# MCU_STM32H723ZGT6.net
KiCad netlist of a schematic drawn in Altium Designer
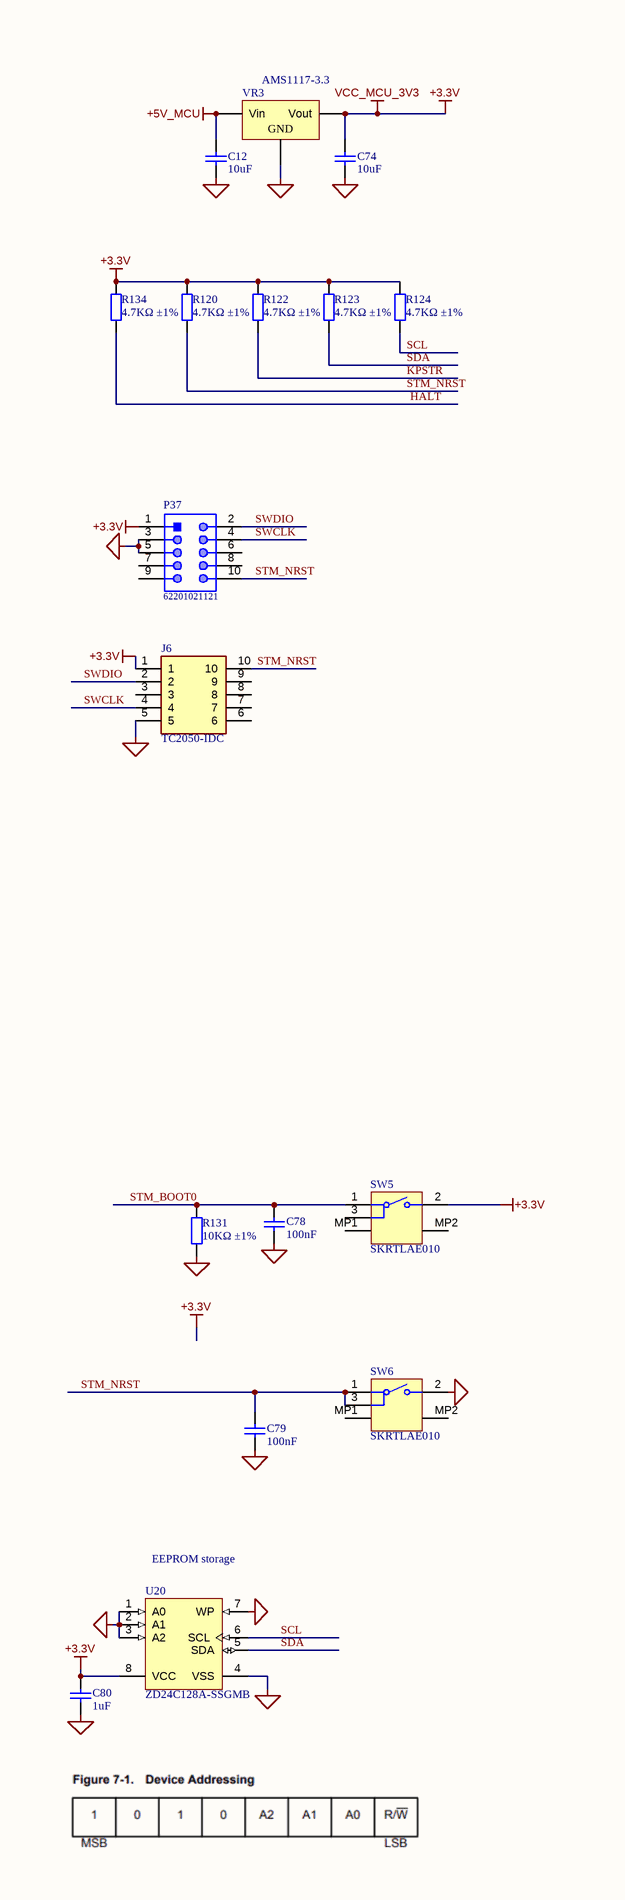
[diagram p0: MCU_STM32H723ZGT6.SchDoc, left]
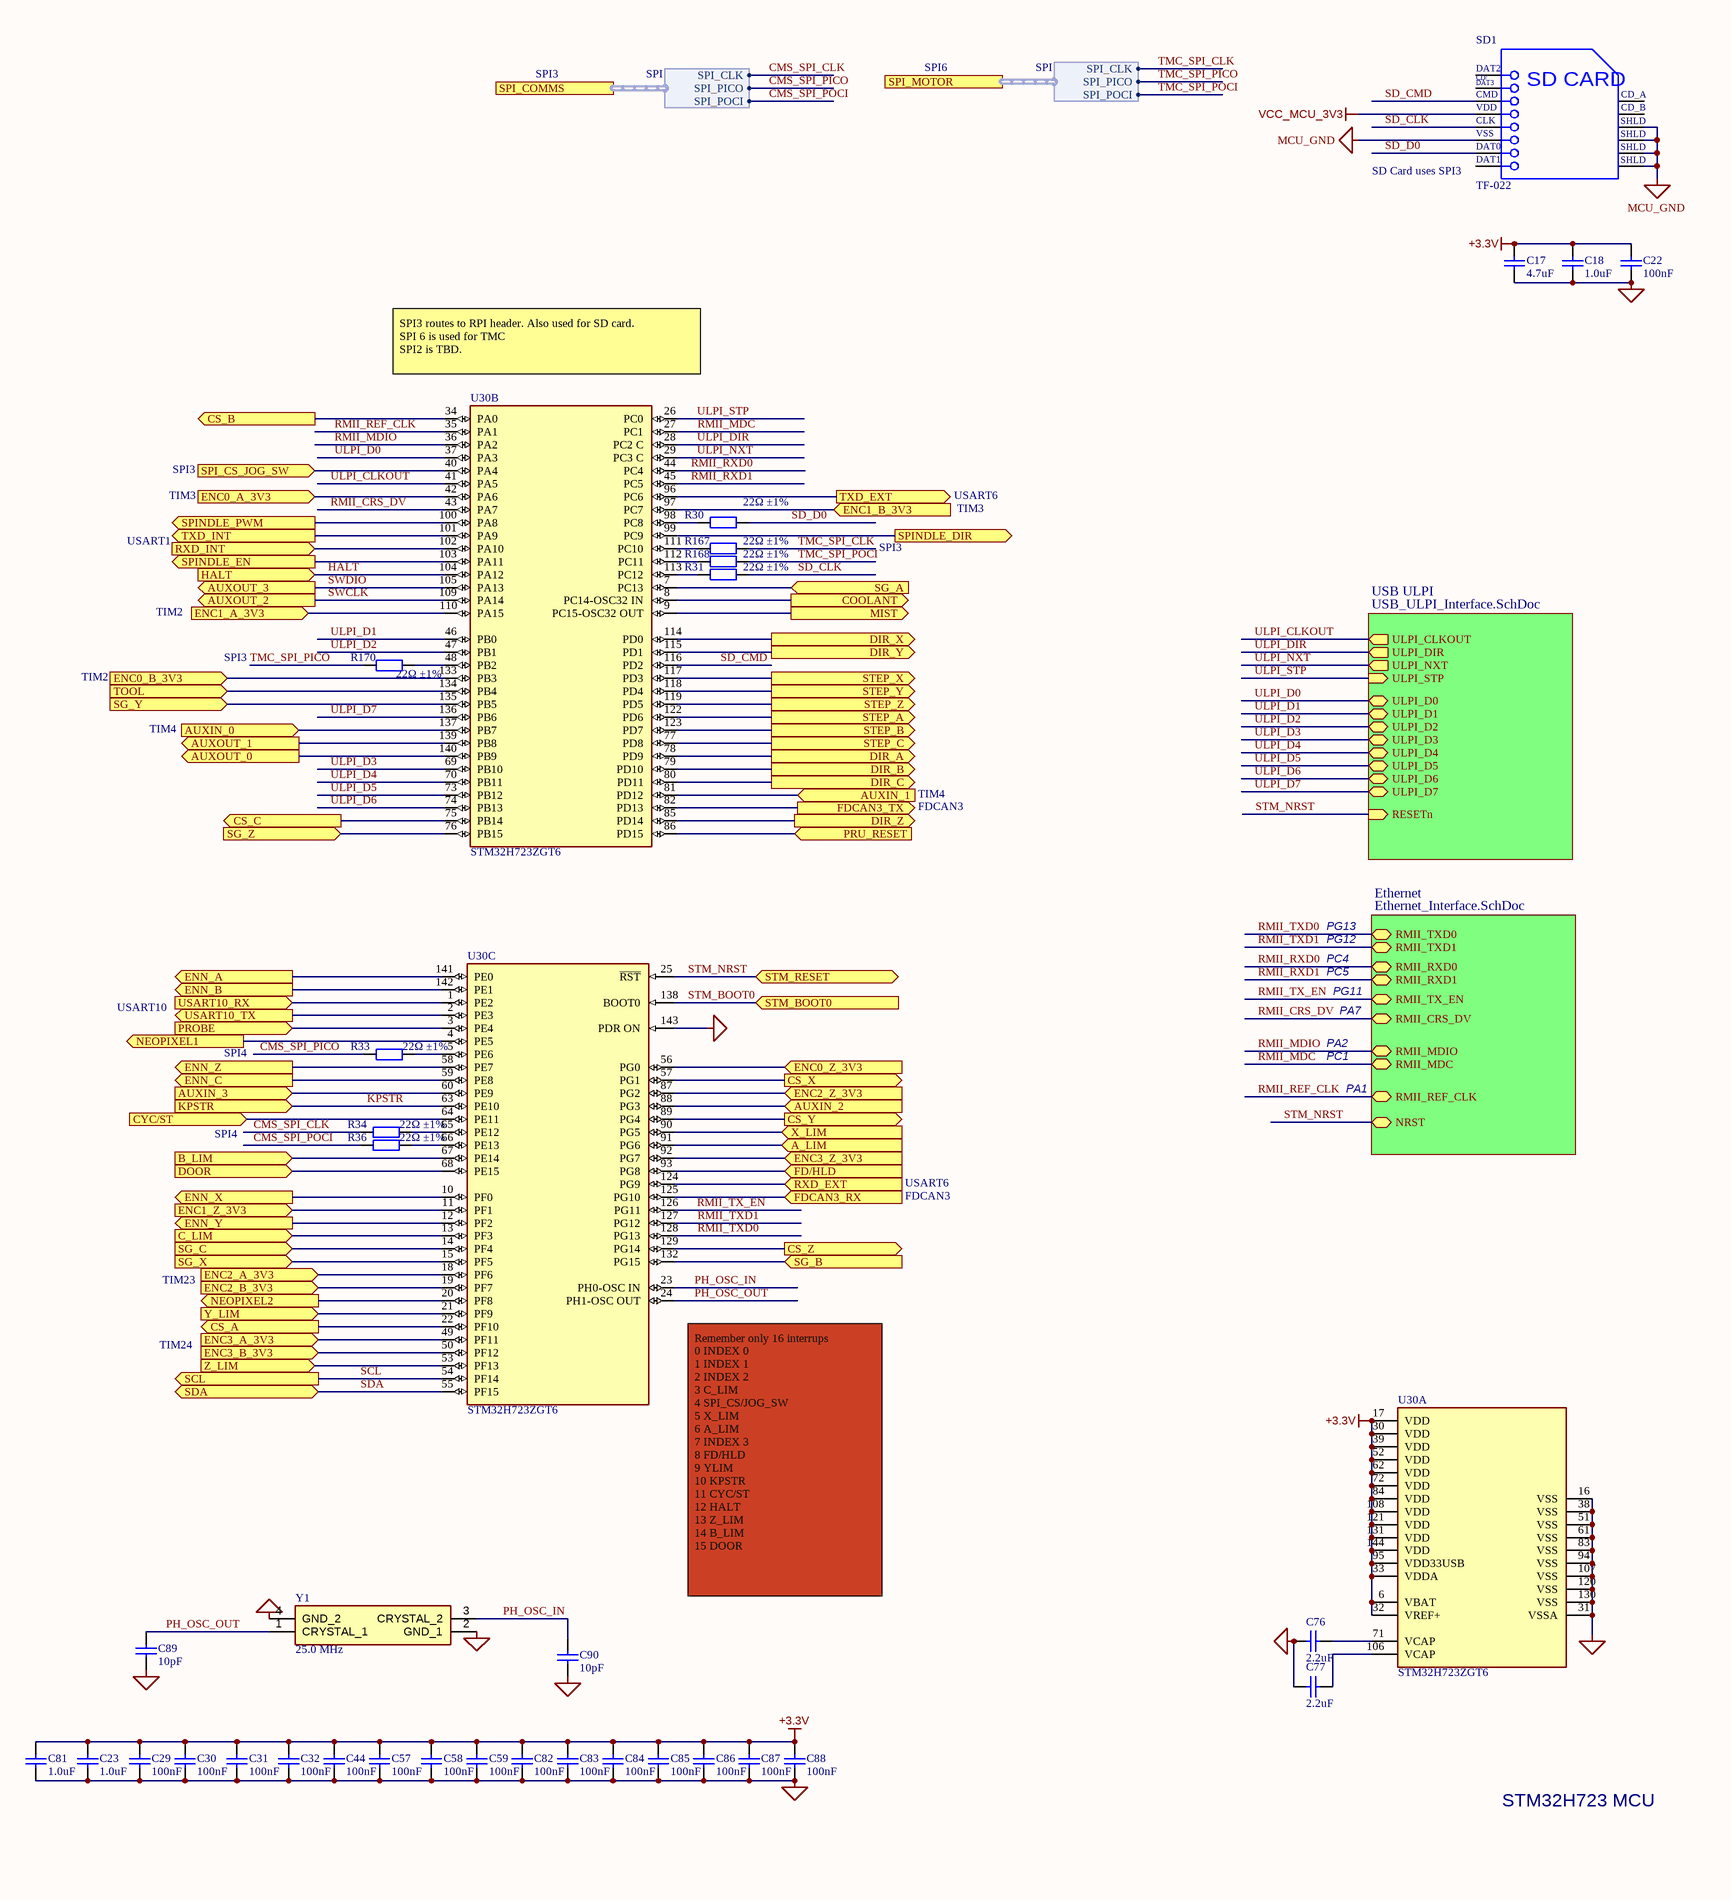
[diagram p1: MCU_STM32H723ZGT6.SchDoc, right]

(export (version "E")
  (design (tool "Eeschema 10.0.6"))
  (components
    (comp (ref "C12")
      (value "10uF")
      (footprint "1206_C")
      (description "Chip capacitors")
      (fields
        (field (name "MANUFACTURER") "Samsung Electro-Mechanics")
        (field (name "PARTNUMBER") "CL31A106KBHNNNE")
      )
      (libsource (lib "Cap") (part "1206 10uF (106) 10% 50V"))
    )
    (comp (ref "C17")
      (value "4.7uF")
      (footprint "0603_C")
      (description "16V 4.7uF X5R ±10% 0603 Multilayer Ceramic Capacitors MLCC - SMD/SMT ROHS")
      (fields (field (name "MANUFACTURER") "Samsung Electro-Mechanics") (field (name "TOLERANCE") "10%"))
      (libsource (lib "Sienci_Labs") (part "0603 4.7uF (475) 10% 16V"))
    )
    (comp (ref "C18")
      (value "1.0uF")
      (footprint "0402_C")
      (description "Chip capacitor")
      (fields (field (name "MANUFACTURER") "Samsung Electro-Mechanics") (field (name "TOLERANCE") "10%"))
      (libsource (lib "Cap") (part "0402 1.0uF (105) 10% 25V"))
    )
    (comp (ref "C22")
      (value "100nF")
      (footprint "0402_C")
      (description "16V 100nF X7R ±10% 0402 Multilayer Ceramic Capacitors MLCC - SMD/SMT ROHS")
      (fields (field (name "MANUFACTURER") "Samsung Electro-Mechanics") (field (name "TOLERANCE") "10%"))
      (libsource (lib "Sienci_Labs") (part "0402 100nF (104) 10% 16V"))
    )
    (comp (ref "C23")
      (value "1.0uF")
      (footprint "0402_C")
      (description "Chip capacitor")
      (fields
        (field (name "MANUFACTURER") "Samsung Electro-Mechanics")
        (field (name "PARTNUMBER") "CL05A105KA5NQNC")
      )
      (libsource (lib "Cap") (part "0402 1.0uF (105) 10% 25V"))
    )
    (comp (ref "C29")
      (value "100nF")
      (footprint "0402_C")
      (description "Chip capacitors")
      (fields
        (field (name "MANUFACTURER") "Samsung Electro-Mechanics")
        (field (name "PARTNUMBER") "CL05B104KO5NNNC")
      )
      (libsource (lib "Cap") (part "0402 100nF (104) 10% 16V"))
    )
    (comp (ref "C30")
      (value "100nF")
      (footprint "0402_C")
      (description "Chip capacitors")
      (fields
        (field (name "MANUFACTURER") "Samsung Electro-Mechanics")
        (field (name "PARTNUMBER") "CL05B104KO5NNNC")
      )
      (libsource (lib "Cap") (part "0402 100nF (104) 10% 16V"))
    )
    (comp (ref "C31")
      (value "100nF")
      (footprint "0402_C")
      (description "Chip capacitors")
      (fields
        (field (name "MANUFACTURER") "Samsung Electro-Mechanics")
        (field (name "PARTNUMBER") "CL05B104KO5NNNC")
      )
      (libsource (lib "Cap") (part "0402 100nF (104) 10% 16V"))
    )
    (comp (ref "C32")
      (value "100nF")
      (footprint "0402_C")
      (description "Chip capacitors")
      (fields
        (field (name "MANUFACTURER") "Samsung Electro-Mechanics")
        (field (name "PARTNUMBER") "CL05B104KO5NNNC")
      )
      (libsource (lib "Cap") (part "0402 100nF (104) 10% 16V"))
    )
    (comp (ref "C44")
      (value "100nF")
      (footprint "0402_C")
      (description "Chip capacitors")
      (fields
        (field (name "MANUFACTURER") "Samsung Electro-Mechanics")
        (field (name "PARTNUMBER") "CL05B104KO5NNNC")
      )
      (libsource (lib "Cap") (part "0402 100nF (104) 10% 16V"))
    )
    (comp (ref "C57")
      (value "100nF")
      (footprint "0402_C")
      (description "Chip capacitors")
      (fields
        (field (name "MANUFACTURER") "Samsung Electro-Mechanics")
        (field (name "PARTNUMBER") "CL05B104KO5NNNC")
      )
      (libsource (lib "Cap") (part "0402 100nF (104) 10% 16V"))
    )
    (comp (ref "C58")
      (value "100nF")
      (footprint "0402_C")
      (description "Chip capacitors")
      (fields
        (field (name "MANUFACTURER") "Samsung Electro-Mechanics")
        (field (name "PARTNUMBER") "CL05B104KO5NNNC")
      )
      (libsource (lib "Cap") (part "0402 100nF (104) 10% 16V"))
    )
    (comp (ref "C59")
      (value "100nF")
      (footprint "0402_C")
      (description "Chip capacitors")
      (fields
        (field (name "MANUFACTURER") "Samsung Electro-Mechanics")
        (field (name "PARTNUMBER") "CL05B104KO5NNNC")
      )
      (libsource (lib "Cap") (part "0402 100nF (104) 10% 16V"))
    )
    (comp (ref "C74")
      (value "10uF")
      (footprint "1206_C")
      (description "Chip capacitors")
      (fields
        (field (name "MANUFACTURER") "Samsung Electro-Mechanics")
        (field (name "PARTNUMBER") "CL31A106KBHNNNE")
      )
      (libsource (lib "Cap") (part "1206 10uF (106) 10% 50V"))
    )
    (comp (ref "C76")
      (value "2.2uF")
      (footprint "0603_C")
      (description "Chip capacitors")
      (fields
        (field (name "MANUFACTURER") "Samsung Electro-Mechanics")
        (field (name "PARTNUMBER") "CL10A225KO8NNNC")
      )
      (libsource (lib "Cap") (part "0603 2.2uF (225) 10% 16V"))
    )
    (comp (ref "C77")
      (value "2.2uF")
      (footprint "0603_C")
      (description "Chip capacitors")
      (fields
        (field (name "MANUFACTURER") "Samsung Electro-Mechanics")
        (field (name "PARTNUMBER") "CL10A225KO8NNNC")
      )
      (libsource (lib "Cap") (part "0603 2.2uF (225) 10% 16V"))
    )
    (comp (ref "C78")
      (value "100nF")
      (footprint "0603_C")
      (description "Chip capacitors")
      (fields (field (name "MANUFACTURER") "YAGEO") (field (name "PARTNUMBER") "CC0603KRX7R9BB104"))
      (libsource (lib "Cap") (part "0603 100nF (104) 10% 50V"))
    )
    (comp (ref "C79")
      (value "100nF")
      (footprint "0603_C")
      (description "Chip capacitors")
      (fields (field (name "MANUFACTURER") "YAGEO") (field (name "PARTNUMBER") "CC0603KRX7R9BB104"))
      (libsource (lib "Cap") (part "0603 100nF (104) 10% 50V"))
    )
    (comp (ref "C80")
      (value "1uF")
      (footprint "0603_C")
      (description "Chip capacitors")
      (fields
        (field (name "MANUFACTURER") "Samsung Electro-Mechanics")
        (field (name "PARTNUMBER") "CL10A105KB8NNNC")
      )
      (libsource (lib "Cap") (part "0603 1uF (105) 10% 50V"))
    )
    (comp (ref "C81")
      (value "1.0uF")
      (footprint "0402_C")
      (description "Chip capacitor")
      (fields
        (field (name "MANUFACTURER") "Samsung Electro-Mechanics")
        (field (name "PARTNUMBER") "CL05A105KA5NQNC")
      )
      (libsource (lib "Cap") (part "0402 1.0uF (105) 10% 25V"))
    )
    (comp (ref "C82")
      (value "100nF")
      (footprint "0402_C")
      (description "Chip capacitors")
      (fields
        (field (name "MANUFACTURER") "Samsung Electro-Mechanics")
        (field (name "PARTNUMBER") "CL05B104KO5NNNC")
      )
      (libsource (lib "Cap") (part "0402 100nF (104) 10% 16V"))
    )
    (comp (ref "C83")
      (value "100nF")
      (footprint "0402_C")
      (description "Chip capacitors")
      (fields
        (field (name "MANUFACTURER") "Samsung Electro-Mechanics")
        (field (name "PARTNUMBER") "CL05B104KO5NNNC")
      )
      (libsource (lib "Cap") (part "0402 100nF (104) 10% 16V"))
    )
    (comp (ref "C84")
      (value "100nF")
      (footprint "0402_C")
      (description "Chip capacitors")
      (fields
        (field (name "MANUFACTURER") "Samsung Electro-Mechanics")
        (field (name "PARTNUMBER") "CL05B104KO5NNNC")
      )
      (libsource (lib "Cap") (part "0402 100nF (104) 10% 16V"))
    )
    (comp (ref "C85")
      (value "100nF")
      (footprint "0402_C")
      (description "Chip capacitors")
      (fields
        (field (name "MANUFACTURER") "Samsung Electro-Mechanics")
        (field (name "PARTNUMBER") "CL05B104KO5NNNC")
      )
      (libsource (lib "Cap") (part "0402 100nF (104) 10% 16V"))
    )
    (comp (ref "C86")
      (value "100nF")
      (footprint "0402_C")
      (description "Chip capacitors")
      (fields
        (field (name "MANUFACTURER") "Samsung Electro-Mechanics")
        (field (name "PARTNUMBER") "CL05B104KO5NNNC")
      )
      (libsource (lib "Cap") (part "0402 100nF (104) 10% 16V"))
    )
    (comp (ref "C87")
      (value "100nF")
      (footprint "0402_C")
      (description "Chip capacitors")
      (fields
        (field (name "MANUFACTURER") "Samsung Electro-Mechanics")
        (field (name "PARTNUMBER") "CL05B104KO5NNNC")
      )
      (libsource (lib "Cap") (part "0402 100nF (104) 10% 16V"))
    )
    (comp (ref "C88")
      (value "100nF")
      (footprint "0402_C")
      (description "Chip capacitors")
      (fields
        (field (name "MANUFACTURER") "Samsung Electro-Mechanics")
        (field (name "PARTNUMBER") "CL05B104KO5NNNC")
      )
      (libsource (lib "Cap") (part "0402 100nF (104) 10% 16V"))
    )
    (comp (ref "C89")
      (value "10pF")
      (footprint "0402_C")
      (description "Chip capacitors")
      (fields
        (field (name "MANUFACTURER") "Samsung Electro-Mechanics")
        (field (name "PARTNUMBER") "CL05C100JB5NNNC")
      )
      (libsource (lib "Cap") (part "0402 10pF (100) 5% 50V"))
    )
    (comp (ref "C90")
      (value "10pF")
      (footprint "0402_C")
      (description "Chip capacitors")
      (fields
        (field (name "MANUFACTURER") "Samsung Electro-Mechanics")
        (field (name "PARTNUMBER") "CL05C100JB5NNNC")
      )
      (libsource (lib "Cap") (part "0402 10pF (100) 5% 50V"))
    )
    (comp (ref "J6")
      (value "TC2050-IDC")
      (footprint "SamacSys:TC2050-IDC")
      (description "Connector")
      (libsource (lib "*") (part "TC2050-IDC"))
    )
    (comp (ref "P37")
      (value "62201021121")
      (footprint "62201021121")
      (description "THT Vertical Pin Header WR-PHD, Pitch 1.27 mm, Dual Row, 10 pins")
      (fields (field (name "MANUFACTURER") "Wurth Elektronik") (field (name "PUBLISHER") "WurthElektronik"))
      (libsource (lib "Altium Content Vault") (part "WE-CN-2P-M-R10"))
    )
    (comp (ref "R30")
      (value "22Ω ±1%")
      (footprint "0402_R")
      (description "Chip resistor")
      (fields (field (name "MANUFACTURER") "Uniroyal Elec") (field (name "PARTNUMBER") "0402WGF220JTCE"))
      (libsource (lib "RES") (part "0402 22R (22R0) 1%"))
    )
    (comp (ref "R31")
      (value "22Ω ±1%")
      (footprint "0402_R")
      (description "Chip resistor")
      (fields (field (name "MANUFACTURER") "Uniroyal Elec") (field (name "PARTNUMBER") "0402WGF220JTCE"))
      (libsource (lib "RES") (part "0402 22R (22R0) 1%"))
    )
    (comp (ref "R33")
      (value "22Ω ±1%")
      (footprint "0402_R")
      (description "Chip resistor")
      (fields (field (name "MANUFACTURER") "Uniroyal Elec") (field (name "PARTNUMBER") "0402WGF220JTCE"))
      (libsource (lib "RES") (part "0402 22R (22R0) 1%"))
    )
    (comp (ref "R34")
      (value "22Ω ±1%")
      (footprint "0402_R")
      (description "Chip resistor")
      (fields (field (name "MANUFACTURER") "Uniroyal Elec") (field (name "PARTNUMBER") "0402WGF220JTCE"))
      (libsource (lib "RES") (part "0402 22R (22R0) 1%"))
    )
    (comp (ref "R36")
      (value "22Ω ±1%")
      (footprint "0402_R")
      (description "Chip resistor")
      (fields (field (name "MANUFACTURER") "Uniroyal Elec") (field (name "PARTNUMBER") "0402WGF220JTCE"))
      (libsource (lib "RES") (part "0402 22R (22R0) 1%"))
    )
    (comp (ref "R120")
      (value "4.7KΩ ±1%")
      (footprint "0603_R")
      (description "Chip resistor")
      (fields (field (name "MANUFACTURER") "Uniroyal Elec") (field (name "PARTNUMBER") "0603WAF4701T5E"))
      (libsource (lib "RES") (part "0603 4.7K (4701) 1%"))
    )
    (comp (ref "R122")
      (value "4.7KΩ ±1%")
      (footprint "0603_R")
      (description "Chip resistor")
      (fields (field (name "MANUFACTURER") "Uniroyal Elec") (field (name "PARTNUMBER") "0603WAF4701T5E"))
      (libsource (lib "RES") (part "0603 4.7K (4701) 1%"))
    )
    (comp (ref "R123")
      (value "4.7KΩ ±1%")
      (footprint "0603_R")
      (description "Chip resistor")
      (fields (field (name "MANUFACTURER") "Uniroyal Elec") (field (name "PARTNUMBER") "0603WAF4701T5E"))
      (libsource (lib "RES") (part "0603 4.7K (4701) 1%"))
    )
    (comp (ref "R124")
      (value "4.7KΩ ±1%")
      (footprint "0603_R")
      (description "Chip resistor")
      (fields (field (name "MANUFACTURER") "Uniroyal Elec") (field (name "PARTNUMBER") "0603WAF4701T5E"))
      (libsource (lib "RES") (part "0603 4.7K (4701) 1%"))
    )
    (comp (ref "R131")
      (value "10KΩ ±1%")
      (footprint "0603_R")
      (description "Chip resistor")
      (fields (field (name "MANUFACTURER") "Uniroyal Elec") (field (name "PARTNUMBER") "0603WAF1002T5E"))
      (libsource (lib "RES") (part "0603 10K (1002) 1%"))
    )
    (comp (ref "R134")
      (value "4.7KΩ ±1%")
      (footprint "0603_R")
      (description "Chip resistor")
      (fields (field (name "MANUFACTURER") "Uniroyal Elec") (field (name "PARTNUMBER") "0603WAF4701T5E"))
      (libsource (lib "RES") (part "0603 4.7K (4701) 1%"))
    )
    (comp (ref "R167")
      (value "22Ω ±1%")
      (footprint "0402_R")
      (description "Chip resistor")
      (fields (field (name "MANUFACTURER") "Uniroyal Elec") (field (name "PARTNUMBER") "0402WGF220JTCE"))
      (libsource (lib "RES") (part "0402 22R (22R0) 1%"))
    )
    (comp (ref "R168")
      (value "22Ω ±1%")
      (footprint "0402_R")
      (description "Chip resistor")
      (fields (field (name "MANUFACTURER") "Uniroyal Elec") (field (name "PARTNUMBER") "0402WGF220JTCE"))
      (libsource (lib "RES") (part "0402 22R (22R0) 1%"))
    )
    (comp (ref "R170")
      (value "22Ω ±1%")
      (footprint "0402_R")
      (description "Chip resistor")
      (fields (field (name "MANUFACTURER") "Uniroyal Elec") (field (name "PARTNUMBER") "0402WGF220JTCE"))
      (libsource (lib "RES") (part "0402 22R (22R0) 1%"))
    )
    (comp (ref "SD1")
      (value "TF-022")
      (footprint "MOLX-503398-1892_V")
      (description "-40℃~+85℃ 1.28mm Gold plating Deck MicroSD card (TF card) Self bomb SMD SD Card Connectors ROHS")
      (fields (field (name "MANUFACTURER") "Hanbo Electronic"))
      (libsource (lib "Sienci_Labs") (part "TF-022"))
    )
    (comp (ref "SW5")
      (value "SKRTLAE010")
      (footprint "ALPS-SKRTLAE010_V")
      (description "Side Push Type, 250 V, -40 to 90 degC, 3-Pin SMD, RoHS, Tape and Reel")
      (fields (field (name "MANUFACTURER") "ALPS"))
      (libsource (lib "Altium Content Vault") (part "SW_SPST-3_A"))
    )
    (comp (ref "SW6")
      (value "SKRTLAE010")
      (footprint "ALPS-SKRTLAE010_V")
      (description "Side Push Type, 250 V, -40 to 90 degC, 3-Pin SMD, RoHS, Tape and Reel")
      (fields (field (name "MANUFACTURER") "ALPS"))
      (libsource (lib "Altium Content Vault") (part "SW_SPST-3_A"))
    )
    (comp (ref "U20")
      (value "ZD24C128A-SSGMB")
      (footprint "SOIC-SN8_L")
      (description "IC EEPROM 128KBIT I2C 8SOIC")
      (libsource (lib "PrintNC_GRBLHAL_Breakout") (part "MEM-SEEPROM-34AA02-IL8"))
    )
    (comp (ref "U30")
      (value "STM32H723ZGT6")
      (footprint "FP-LQFP144-1A-IPC_A")
      (description "IC MCU 32BIT 1MB FLASH 144LQFP")
      (libsource (lib "Universal_CNC_Breakout") (part "STM32H723ZGT6"))
    )
    (comp (ref "VR3")
      (value "AMS1117-3.3")
      (footprint "SOT-223")
      (description "Vout=3.3V 1A 72dB@(120Hz) (LDO)")
      (libsource (lib "LDO") (part "SOT-223 AMS1117-3.3"))
    )
    (comp (ref "Y1")
      (value "25.0 MHz")
      (footprint "SamacSys:YSX321SL")
      (description "Crystal or Oscillator")
      (fields (field (name "MANUFACTURER_PART_NUMBER") "X322525MSB4SI"))
      (libsource (lib "*") (part "YSX321SL"))
    )
  )
  (nets
    (net (code "2") (name "+3.3V") (class "Default")
      (node (ref "C17") (pin "2") (pinfunction "2_2") (pintype "passive"))
      (node (ref "C18") (pin "2") (pinfunction "2_2") (pintype "passive"))
      (node (ref "C22") (pin "2") (pinfunction "2_2") (pintype "passive"))
      (node (ref "C23") (pin "2") (pinfunction "2_2") (pintype "passive"))
      (node (ref "C29") (pin "2") (pinfunction "2_2") (pintype "passive"))
      (node (ref "C30") (pin "2") (pinfunction "2_2") (pintype "passive"))
      (node (ref "C31") (pin "2") (pinfunction "2_2") (pintype "passive"))
      (node (ref "C32") (pin "2") (pinfunction "2_2") (pintype "passive"))
      (node (ref "C44") (pin "2") (pinfunction "2_2") (pintype "passive"))
      (node (ref "C57") (pin "2") (pinfunction "2_2") (pintype "passive"))
      (node (ref "C58") (pin "2") (pinfunction "2_2") (pintype "passive"))
      (node (ref "C59") (pin "2") (pinfunction "2_2") (pintype "passive"))
      (node (ref "C74") (pin "2") (pinfunction "2_2") (pintype "passive"))
      (node (ref "C80") (pin "2") (pinfunction "2_2") (pintype "passive"))
      (node (ref "C81") (pin "2") (pinfunction "2_2") (pintype "passive"))
      (node (ref "C82") (pin "2") (pinfunction "2_2") (pintype "passive"))
      (node (ref "C83") (pin "2") (pinfunction "2_2") (pintype "passive"))
      (node (ref "C84") (pin "2") (pinfunction "2_2") (pintype "passive"))
      (node (ref "C85") (pin "2") (pinfunction "2_2") (pintype "passive"))
      (node (ref "C86") (pin "2") (pinfunction "2_2") (pintype "passive"))
      (node (ref "C87") (pin "2") (pinfunction "2_2") (pintype "passive"))
      (node (ref "C88") (pin "2") (pinfunction "2_2") (pintype "passive"))
      (node (ref "J6") (pin "1") (pinfunction "1_1") (pintype "passive"))
      (node (ref "P37") (pin "1") (pinfunction "1_1") (pintype "passive"))
      (node (ref "R120") (pin "2") (pinfunction "2_2") (pintype "passive"))
      (node (ref "R122") (pin "2") (pinfunction "2_2") (pintype "passive"))
      (node (ref "R123") (pin "2") (pinfunction "2_2") (pintype "passive"))
      (node (ref "R124") (pin "2") (pinfunction "2_2") (pintype "passive"))
      (node (ref "R134") (pin "2") (pinfunction "2_2") (pintype "passive"))
      (node (ref "SD1") (pin "4") (pinfunction "VDD_4") (pintype "passive"))
      (node (ref "SW5") (pin "2") (pinfunction "2_2") (pintype "passive"))
      (node (ref "U20") (pin "8") (pinfunction "VCC_8") (pintype "power_in"))
      (node (ref "U30") (pin "108") (pinfunction "VDD_108") (pintype "power_in"))
      (node (ref "U30") (pin "121") (pinfunction "VDD_121") (pintype "power_in"))
      (node (ref "U30") (pin "131") (pinfunction "VDD_131") (pintype "power_in"))
      (node (ref "U30") (pin "144") (pinfunction "VDD_144") (pintype "power_in"))
      (node (ref "U30") (pin "17") (pinfunction "VDD_17") (pintype "power_in"))
      (node (ref "U30") (pin "30") (pinfunction "VDD_30") (pintype "power_in"))
      (node (ref "U30") (pin "32") (pinfunction "VREF+_32") (pintype "power_in"))
      (node (ref "U30") (pin "33") (pinfunction "VDDA_33") (pintype "power_in"))
      (node (ref "U30") (pin "39") (pinfunction "VDD_39") (pintype "power_in"))
      (node (ref "U30") (pin "52") (pinfunction "VDD_52") (pintype "power_in"))
      (node (ref "U30") (pin "6") (pinfunction "VBAT_6") (pintype "power_in"))
      (node (ref "U30") (pin "62") (pinfunction "VDD_62") (pintype "power_in"))
      (node (ref "U30") (pin "72") (pinfunction "VDD_72") (pintype "power_in"))
      (node (ref "U30") (pin "84") (pinfunction "VDD_84") (pintype "power_in"))
      (node (ref "U30") (pin "95") (pinfunction "VDD33USB_95") (pintype "power_in"))
      (node (ref "VR3") (pin "2") (pinfunction "Vout_2") (pintype "passive"))
    )
    (net (code "3") (name "+5V_MCU") (class "Default")
      (node (ref "C12") (pin "2") (pinfunction "2_2") (pintype "passive"))
      (node (ref "VR3") (pin "3") (pinfunction "Vin_3") (pintype "passive"))
    )
    (net (code "4") (name "/AUXIN_0") (class "Default")
      (node (ref "U30") (pin "137") (pinfunction "PB7_137") (pintype "bidirectional"))
    )
    (net (code "5") (name "/AUXIN_1") (class "Default")
      (node (ref "U30") (pin "81") (pinfunction "PD12_81") (pintype "bidirectional"))
    )
    (net (code "6") (name "/AUXIN_2") (class "Default")
      (node (ref "U30") (pin "88") (pinfunction "PG3_88") (pintype "bidirectional"))
    )
    (net (code "7") (name "/AUXIN_3") (class "Default")
      (node (ref "U30") (pin "60") (pinfunction "PE9_60") (pintype "bidirectional"))
    )
    (net (code "8") (name "/AUXOUT_0") (class "Default")
      (node (ref "U30") (pin "140") (pinfunction "PB9_140") (pintype "bidirectional"))
    )
    (net (code "9") (name "/AUXOUT_1") (class "Default")
      (node (ref "U30") (pin "139") (pinfunction "PB8_139") (pintype "bidirectional"))
    )
    (net (code "10") (name "/A_LIM") (class "Default")
      (node (ref "U30") (pin "91") (pinfunction "PG6_91") (pintype "bidirectional"))
    )
    (net (code "11") (name "/B_LIM") (class "Default")
      (node (ref "U30") (pin "67") (pinfunction "PE14_67") (pintype "bidirectional"))
    )
    (net (code "12") (name "/CMS_SPI_CLK") (class "Default")
      (node (ref "R34") (pin "1") (pinfunction "1_1") (pintype "passive"))
    )
    (net (code "13") (name "/CMS_SPI_PICO") (class "Default")
      (node (ref "R33") (pin "1") (pinfunction "1_1") (pintype "passive"))
    )
    (net (code "14") (name "/CMS_SPI_POCI") (class "Default")
      (node (ref "R36") (pin "1") (pinfunction "1_1") (pintype "passive"))
    )
    (net (code "15") (name "/COOLANT") (class "Default")
      (node (ref "U30") (pin "8") (pinfunction "PC14-OSC32_IN_8") (pintype "bidirectional"))
    )
    (net (code "16") (name "/CS_A") (class "Default")
      (node (ref "U30") (pin "22") (pinfunction "PF10_22") (pintype "bidirectional"))
    )
    (net (code "17") (name "/CS_B") (class "Default")
      (node (ref "U30") (pin "34") (pinfunction "PA0_34") (pintype "bidirectional"))
    )
    (net (code "18") (name "/CS_C") (class "Default")
      (node (ref "U30") (pin "75") (pinfunction "PB14_75") (pintype "bidirectional"))
    )
    (net (code "19") (name "/CS_X") (class "Default")
      (node (ref "U30") (pin "57") (pinfunction "PG1_57") (pintype "bidirectional"))
    )
    (net (code "20") (name "/CS_Y") (class "Default")
      (node (ref "U30") (pin "89") (pinfunction "PG4_89") (pintype "bidirectional"))
    )
    (net (code "21") (name "/CS_Z") (class "Default")
      (node (ref "U30") (pin "129") (pinfunction "PG14_129") (pintype "bidirectional"))
    )
    (net (code "22") (name "/CYC{slash}ST") (class "Default")
      (node (ref "U30") (pin "64") (pinfunction "PE11_64") (pintype "bidirectional"))
    )
    (net (code "23") (name "/C_LIM") (class "Default")
      (node (ref "U30") (pin "13") (pinfunction "PF3_13") (pintype "bidirectional"))
    )
    (net (code "24") (name "/DIR_A") (class "Default")
      (node (ref "U30") (pin "78") (pinfunction "PD9_78") (pintype "bidirectional"))
    )
    (net (code "25") (name "/DIR_B") (class "Default")
      (node (ref "U30") (pin "79") (pinfunction "PD10_79") (pintype "bidirectional"))
    )
    (net (code "26") (name "/DIR_C") (class "Default")
      (node (ref "U30") (pin "80") (pinfunction "PD11_80") (pintype "bidirectional"))
    )
    (net (code "27") (name "/DIR_X") (class "Default")
      (node (ref "U30") (pin "114") (pinfunction "PD0_114") (pintype "bidirectional"))
    )
    (net (code "28") (name "/DIR_Y") (class "Default")
      (node (ref "U30") (pin "115") (pinfunction "PD1_115") (pintype "bidirectional"))
    )
    (net (code "29") (name "/DIR_Z") (class "Default")
      (node (ref "U30") (pin "85") (pinfunction "PD14_85") (pintype "bidirectional"))
    )
    (net (code "30") (name "/DOOR") (class "Default")
      (node (ref "U30") (pin "68") (pinfunction "PE15_68") (pintype "bidirectional"))
    )
    (net (code "31") (name "/ENC0_A_3V3") (class "Default")
      (node (ref "U30") (pin "42") (pinfunction "PA6_42") (pintype "bidirectional"))
    )
    (net (code "32") (name "/ENC0_B_3V3") (class "Default")
      (node (ref "U30") (pin "133") (pinfunction "PB3_133") (pintype "bidirectional"))
    )
    (net (code "33") (name "/ENC0_Z_3V3") (class "Default")
      (node (ref "U30") (pin "56") (pinfunction "PG0_56") (pintype "bidirectional"))
    )
    (net (code "34") (name "/ENC1_A_3V3") (class "Default")
      (node (ref "U30") (pin "110") (pinfunction "PA15_110") (pintype "bidirectional"))
    )
    (net (code "35") (name "/ENC1_B_3V3") (class "Default")
      (node (ref "U30") (pin "97") (pinfunction "PC7_97") (pintype "bidirectional"))
    )
    (net (code "36") (name "/ENC1_Z_3V3") (class "Default")
      (node (ref "U30") (pin "11") (pinfunction "PF1_11") (pintype "bidirectional"))
    )
    (net (code "37") (name "/ENC2_A_3V3") (class "Default")
      (node (ref "U30") (pin "18") (pinfunction "PF6_18") (pintype "bidirectional"))
    )
    (net (code "38") (name "/ENC2_B_3V3") (class "Default")
      (node (ref "U30") (pin "19") (pinfunction "PF7_19") (pintype "bidirectional"))
    )
    (net (code "39") (name "/ENC2_Z_3V3") (class "Default")
      (node (ref "U30") (pin "87") (pinfunction "PG2_87") (pintype "bidirectional"))
    )
    (net (code "40") (name "/ENC3_A_3V3") (class "Default")
      (node (ref "U30") (pin "49") (pinfunction "PF11_49") (pintype "bidirectional"))
    )
    (net (code "41") (name "/ENC3_B_3V3") (class "Default")
      (node (ref "U30") (pin "50") (pinfunction "PF12_50") (pintype "bidirectional"))
    )
    (net (code "42") (name "/ENC3_Z_3V3") (class "Default")
      (node (ref "U30") (pin "92") (pinfunction "PG7_92") (pintype "bidirectional"))
    )
    (net (code "43") (name "/ENN_A") (class "Default")
      (node (ref "U30") (pin "141") (pinfunction "PE0_141") (pintype "bidirectional"))
    )
    (net (code "44") (name "/ENN_B") (class "Default")
      (node (ref "U30") (pin "142") (pinfunction "PE1_142") (pintype "bidirectional"))
    )
    (net (code "45") (name "/ENN_C") (class "Default")
      (node (ref "U30") (pin "59") (pinfunction "PE8_59") (pintype "bidirectional"))
    )
    (net (code "46") (name "/ENN_X") (class "Default")
      (node (ref "U30") (pin "10") (pinfunction "PF0_10") (pintype "bidirectional"))
    )
    (net (code "47") (name "/ENN_Y") (class "Default")
      (node (ref "U30") (pin "12") (pinfunction "PF2_12") (pintype "bidirectional"))
    )
    (net (code "48") (name "/ENN_Z") (class "Default")
      (node (ref "U30") (pin "58") (pinfunction "PE7_58") (pintype "bidirectional"))
    )
    (net (code "49") (name "/FDCAN3_RX") (class "Default")
      (node (ref "U30") (pin "125") (pinfunction "PG10_125") (pintype "bidirectional"))
    )
    (net (code "50") (name "/FDCAN3_TX") (class "Default")
      (node (ref "U30") (pin "82") (pinfunction "PD13_82") (pintype "bidirectional"))
    )
    (net (code "51") (name "/FD{slash}HLD") (class "Default")
      (node (ref "U30") (pin "93") (pinfunction "PG8_93") (pintype "bidirectional"))
    )
    (net (code "52") (name "/HALT") (class "Default")
      (node (ref "R134") (pin "1") (pinfunction "1_1") (pintype "passive"))
      (node (ref "U30") (pin "104") (pinfunction "PA12_104") (pintype "bidirectional"))
    )
    (net (code "53") (name "/KPSTR") (class "Default")
      (node (ref "R122") (pin "1") (pinfunction "1_1") (pintype "passive"))
      (node (ref "U30") (pin "63") (pinfunction "PE10_63") (pintype "bidirectional"))
    )
    (net (code "54") (name "/MIST") (class "Default")
      (node (ref "U30") (pin "9") (pinfunction "PC15-OSC32_OUT_9") (pintype "bidirectional"))
    )
    (net (code "55") (name "/NEOPIXEL1") (class "Default")
      (node (ref "U30") (pin "4") (pinfunction "PE5_4") (pintype "bidirectional"))
    )
    (net (code "56") (name "/NEOPIXEL2") (class "Default")
      (node (ref "U30") (pin "20") (pinfunction "PF8_20") (pintype "bidirectional"))
    )
    (net (code "57") (name "/PH_OSC_IN") (class "Default")
      (node (ref "C90") (pin "2") (pinfunction "2_2") (pintype "passive"))
      (node (ref "U30") (pin "23") (pinfunction "PH0-OSC_IN_23") (pintype "bidirectional"))
      (node (ref "Y1") (pin "3") (pinfunction "CRYSTAL_2_3") (pintype "passive"))
    )
    (net (code "58") (name "/PH_OSC_OUT") (class "Default")
      (node (ref "C89") (pin "2") (pinfunction "2_2") (pintype "passive"))
      (node (ref "U30") (pin "24") (pinfunction "PH1-OSC_OUT_24") (pintype "bidirectional"))
      (node (ref "Y1") (pin "1") (pinfunction "CRYSTAL_1_1") (pintype "passive"))
    )
    (net (code "59") (name "/PROBE") (class "Default")
      (node (ref "U30") (pin "3") (pinfunction "PE4_3") (pintype "bidirectional"))
    )
    (net (code "60") (name "/PRU_RESET") (class "Default")
      (node (ref "U30") (pin "86") (pinfunction "PD15_86") (pintype "bidirectional"))
    )
    (net (code "61") (name "/RMII_CRS_DV") (class "Default")
      (node (ref "U30") (pin "43") (pinfunction "PA7_43") (pintype "bidirectional"))
    )
    (net (code "62") (name "/RMII_MDC") (class "Default")
      (node (ref "U30") (pin "27") (pinfunction "PC1_27") (pintype "bidirectional"))
    )
    (net (code "63") (name "/RMII_MDIO") (class "Default")
      (node (ref "U30") (pin "36") (pinfunction "PA2_36") (pintype "bidirectional"))
    )
    (net (code "64") (name "/RMII_REF_CLK") (class "Default")
      (node (ref "U30") (pin "35") (pinfunction "PA1_35") (pintype "bidirectional"))
    )
    (net (code "65") (name "/RMII_RXD0") (class "Default")
      (node (ref "U30") (pin "44") (pinfunction "PC4_44") (pintype "bidirectional"))
    )
    (net (code "66") (name "/RMII_RXD1") (class "Default")
      (node (ref "U30") (pin "45") (pinfunction "PC5_45") (pintype "bidirectional"))
    )
    (net (code "67") (name "/RMII_TXD0") (class "Default")
      (node (ref "U30") (pin "128") (pinfunction "PG13_128") (pintype "bidirectional"))
    )
    (net (code "68") (name "/RMII_TXD1") (class "Default")
      (node (ref "U30") (pin "127") (pinfunction "PG12_127") (pintype "bidirectional"))
    )
    (net (code "69") (name "/RMII_TX_EN") (class "Default")
      (node (ref "U30") (pin "126") (pinfunction "PG11_126") (pintype "bidirectional"))
    )
    (net (code "70") (name "/RXD_EXT") (class "Default")
      (node (ref "U30") (pin "124") (pinfunction "PG9_124") (pintype "bidirectional"))
    )
    (net (code "71") (name "/RXD_INT") (class "Default")
      (node (ref "U30") (pin "102") (pinfunction "PA10_102") (pintype "bidirectional"))
    )
    (net (code "72") (name "/SCL") (class "Default")
      (node (ref "R124") (pin "1") (pinfunction "1_1") (pintype "passive"))
      (node (ref "U20") (pin "6") (pinfunction "SCL_6") (pintype "input"))
      (node (ref "U30") (pin "54") (pinfunction "PF14_54") (pintype "bidirectional"))
    )
    (net (code "73") (name "/SDA") (class "Default")
      (node (ref "R123") (pin "1") (pinfunction "1_1") (pintype "passive"))
      (node (ref "U20") (pin "5") (pinfunction "SDA_5") (pintype "bidirectional"))
      (node (ref "U30") (pin "55") (pinfunction "PF15_55") (pintype "bidirectional"))
    )
    (net (code "74") (name "/SD_CLK") (class "Default")
      (node (ref "R31") (pin "2") (pinfunction "2_2") (pintype "passive"))
      (node (ref "SD1") (pin "5") (pinfunction "CLK_5") (pintype "passive"))
    )
    (net (code "75") (name "/SD_CMD") (class "Default")
      (node (ref "SD1") (pin "3") (pinfunction "CMD_3") (pintype "passive"))
      (node (ref "U30") (pin "116") (pinfunction "PD2_116") (pintype "bidirectional"))
    )
    (net (code "76") (name "/SD_D0") (class "Default")
      (node (ref "R30") (pin "2") (pinfunction "2_2") (pintype "passive"))
      (node (ref "SD1") (pin "7") (pinfunction "DAT0_7") (pintype "passive"))
    )
    (net (code "77") (name "/SG_A") (class "Default")
      (node (ref "U30") (pin "7") (pinfunction "PC13_7") (pintype "bidirectional"))
    )
    (net (code "78") (name "/SG_B") (class "Default")
      (node (ref "U30") (pin "132") (pinfunction "PG15_132") (pintype "bidirectional"))
    )
    (net (code "79") (name "/SG_C") (class "Default")
      (node (ref "U30") (pin "14") (pinfunction "PF4_14") (pintype "bidirectional"))
    )
    (net (code "80") (name "/SG_X") (class "Default")
      (node (ref "U30") (pin "15") (pinfunction "PF5_15") (pintype "bidirectional"))
    )
    (net (code "81") (name "/SG_Y") (class "Default")
      (node (ref "U30") (pin "135") (pinfunction "PB5_135") (pintype "bidirectional"))
    )
    (net (code "82") (name "/SG_Z") (class "Default")
      (node (ref "U30") (pin "76") (pinfunction "PB15_76") (pintype "bidirectional"))
    )
    (net (code "83") (name "/SPINDLE_DIR") (class "Default")
      (node (ref "U30") (pin "99") (pinfunction "PC9_99") (pintype "bidirectional"))
    )
    (net (code "84") (name "/SPINDLE_EN") (class "Default")
      (node (ref "U30") (pin "103") (pinfunction "PA11_103") (pintype "bidirectional"))
    )
    (net (code "85") (name "/SPINDLE_PWM") (class "Default")
      (node (ref "U30") (pin "100") (pinfunction "PA8_100") (pintype "bidirectional"))
    )
    (net (code "86") (name "/SPI_CS_JOG_SW") (class "Default")
      (node (ref "U30") (pin "40") (pinfunction "PA4_40") (pintype "bidirectional"))
    )
    (net (code "87") (name "/STEP_A") (class "Default")
      (node (ref "U30") (pin "122") (pinfunction "PD6_122") (pintype "bidirectional"))
    )
    (net (code "88") (name "/STEP_B") (class "Default")
      (node (ref "U30") (pin "123") (pinfunction "PD7_123") (pintype "bidirectional"))
    )
    (net (code "89") (name "/STEP_C") (class "Default")
      (node (ref "U30") (pin "77") (pinfunction "PD8_77") (pintype "bidirectional"))
    )
    (net (code "90") (name "/STEP_X") (class "Default")
      (node (ref "U30") (pin "117") (pinfunction "PD3_117") (pintype "bidirectional"))
    )
    (net (code "91") (name "/STEP_Y") (class "Default")
      (node (ref "U30") (pin "118") (pinfunction "PD4_118") (pintype "bidirectional"))
    )
    (net (code "92") (name "/STEP_Z") (class "Default")
      (node (ref "U30") (pin "119") (pinfunction "PD5_119") (pintype "bidirectional"))
    )
    (net (code "93") (name "/STM_BOOT0") (class "Default")
      (node (ref "C78") (pin "2") (pinfunction "2_2") (pintype "passive"))
      (node (ref "R131") (pin "1") (pinfunction "1_1") (pintype "passive"))
      (node (ref "SW5") (pin "1") (pinfunction "1_1") (pintype "passive"))
      (node (ref "U30") (pin "138") (pinfunction "BOOT0_138") (pintype "input"))
    )
    (net (code "94") (name "/STM_NRST") (class "Default")
      (node (ref "C79") (pin "2") (pinfunction "2_2") (pintype "passive"))
      (node (ref "J6") (pin "10") (pinfunction "10_10") (pintype "passive"))
      (node (ref "P37") (pin "10") (pinfunction "10_10") (pintype "passive"))
      (node (ref "R120") (pin "1") (pinfunction "1_1") (pintype "passive"))
      (node (ref "SW6") (pin "1") (pinfunction "1_1") (pintype "passive"))
      (node (ref "SW6") (pin "3") (pinfunction "3_3") (pintype "passive"))
      (node (ref "U30") (pin "25") (pinfunction "~{RST}_25") (pintype "input"))
    )
    (net (code "95") (name "/SWCLK") (class "Default")
      (node (ref "J6") (pin "4") (pinfunction "4_4") (pintype "passive"))
      (node (ref "P37") (pin "4") (pinfunction "4_4") (pintype "passive"))
      (node (ref "U30") (pin "109") (pinfunction "PA14_109") (pintype "bidirectional"))
    )
    (net (code "96") (name "/SWDIO") (class "Default")
      (node (ref "J6") (pin "2") (pinfunction "2_2") (pintype "passive"))
      (node (ref "P37") (pin "2") (pinfunction "2_2") (pintype "passive"))
      (node (ref "U30") (pin "105") (pinfunction "PA13_105") (pintype "bidirectional"))
    )
    (net (code "97") (name "/TMC_SPI_CLK") (class "Default")
      (node (ref "R167") (pin "2") (pinfunction "2_2") (pintype "passive"))
    )
    (net (code "98") (name "/TMC_SPI_PICO") (class "Default")
      (node (ref "R170") (pin "1") (pinfunction "1_1") (pintype "passive"))
    )
    (net (code "99") (name "/TMC_SPI_POCI") (class "Default")
      (node (ref "R168") (pin "2") (pinfunction "2_2") (pintype "passive"))
    )
    (net (code "100") (name "/TOOL") (class "Default")
      (node (ref "U30") (pin "134") (pinfunction "PB4_134") (pintype "bidirectional"))
    )
    (net (code "101") (name "/TXD_EXT") (class "Default")
      (node (ref "U30") (pin "96") (pinfunction "PC6_96") (pintype "bidirectional"))
    )
    (net (code "102") (name "/TXD_INT") (class "Default")
      (node (ref "U30") (pin "101") (pinfunction "PA9_101") (pintype "bidirectional"))
    )
    (net (code "103") (name "/ULPI_CLKOUT") (class "Default")
      (node (ref "U30") (pin "41") (pinfunction "PA5_41") (pintype "bidirectional"))
    )
    (net (code "104") (name "/ULPI_D0") (class "Default")
      (node (ref "U30") (pin "37") (pinfunction "PA3_37") (pintype "bidirectional"))
    )
    (net (code "105") (name "/ULPI_D1") (class "Default")
      (node (ref "U30") (pin "46") (pinfunction "PB0_46") (pintype "bidirectional"))
    )
    (net (code "106") (name "/ULPI_D2") (class "Default")
      (node (ref "U30") (pin "47") (pinfunction "PB1_47") (pintype "bidirectional"))
    )
    (net (code "107") (name "/ULPI_D3") (class "Default")
      (node (ref "U30") (pin "69") (pinfunction "PB10_69") (pintype "bidirectional"))
    )
    (net (code "108") (name "/ULPI_D4") (class "Default")
      (node (ref "U30") (pin "70") (pinfunction "PB11_70") (pintype "bidirectional"))
    )
    (net (code "109") (name "/ULPI_D5") (class "Default")
      (node (ref "U30") (pin "73") (pinfunction "PB12_73") (pintype "bidirectional"))
    )
    (net (code "110") (name "/ULPI_D6") (class "Default")
      (node (ref "U30") (pin "74") (pinfunction "PB13_74") (pintype "bidirectional"))
    )
    (net (code "111") (name "/ULPI_D7") (class "Default")
      (node (ref "U30") (pin "136") (pinfunction "PB6_136") (pintype "bidirectional"))
    )
    (net (code "112") (name "/ULPI_DIR") (class "Default")
      (node (ref "U30") (pin "28") (pinfunction "PC2_C_28") (pintype "bidirectional"))
    )
    (net (code "113") (name "/ULPI_NXT") (class "Default")
      (node (ref "U30") (pin "29") (pinfunction "PC3_C_29") (pintype "bidirectional"))
    )
    (net (code "114") (name "/ULPI_STP") (class "Default")
      (node (ref "U30") (pin "26") (pinfunction "PC0_26") (pintype "bidirectional"))
    )
    (net (code "115") (name "/USART10_RX") (class "Default")
      (node (ref "U30") (pin "1") (pinfunction "PE2_1") (pintype "bidirectional"))
    )
    (net (code "116") (name "/USART10_TX") (class "Default")
      (node (ref "U30") (pin "2") (pinfunction "PE3_2") (pintype "bidirectional"))
    )
    (net (code "117") (name "/X_LIM") (class "Default")
      (node (ref "U30") (pin "90") (pinfunction "PG5_90") (pintype "bidirectional"))
    )
    (net (code "118") (name "/Y_LIM") (class "Default")
      (node (ref "U30") (pin "21") (pinfunction "PF9_21") (pintype "bidirectional"))
    )
    (net (code "119") (name "/Z_LIM") (class "Default")
      (node (ref "U30") (pin "53") (pinfunction "PF13_53") (pintype "bidirectional"))
    )
    (net (code "121") (name "MCU_GND") (class "Default")
      (node (ref "C12") (pin "1") (pinfunction "1_1") (pintype "passive"))
      (node (ref "C17") (pin "1") (pinfunction "1_1") (pintype "passive"))
      (node (ref "C18") (pin "1") (pinfunction "1_1") (pintype "passive"))
      (node (ref "C22") (pin "1") (pinfunction "1_1") (pintype "passive"))
      (node (ref "C23") (pin "1") (pinfunction "1_1") (pintype "passive"))
      (node (ref "C29") (pin "1") (pinfunction "1_1") (pintype "passive"))
      (node (ref "C30") (pin "1") (pinfunction "1_1") (pintype "passive"))
      (node (ref "C31") (pin "1") (pinfunction "1_1") (pintype "passive"))
      (node (ref "C32") (pin "1") (pinfunction "1_1") (pintype "passive"))
      (node (ref "C44") (pin "1") (pinfunction "1_1") (pintype "passive"))
      (node (ref "C57") (pin "1") (pinfunction "1_1") (pintype "passive"))
      (node (ref "C58") (pin "1") (pinfunction "1_1") (pintype "passive"))
      (node (ref "C59") (pin "1") (pinfunction "1_1") (pintype "passive"))
      (node (ref "C74") (pin "1") (pinfunction "1_1") (pintype "passive"))
      (node (ref "C76") (pin "1") (pinfunction "1_1") (pintype "passive"))
      (node (ref "C77") (pin "1") (pinfunction "1_1") (pintype "passive"))
      (node (ref "C78") (pin "1") (pinfunction "1_1") (pintype "passive"))
      (node (ref "C79") (pin "1") (pinfunction "1_1") (pintype "passive"))
      (node (ref "C80") (pin "1") (pinfunction "1_1") (pintype "passive"))
      (node (ref "C81") (pin "1") (pinfunction "1_1") (pintype "passive"))
      (node (ref "C82") (pin "1") (pinfunction "1_1") (pintype "passive"))
      (node (ref "C83") (pin "1") (pinfunction "1_1") (pintype "passive"))
      (node (ref "C84") (pin "1") (pinfunction "1_1") (pintype "passive"))
      (node (ref "C85") (pin "1") (pinfunction "1_1") (pintype "passive"))
      (node (ref "C86") (pin "1") (pinfunction "1_1") (pintype "passive"))
      (node (ref "C87") (pin "1") (pinfunction "1_1") (pintype "passive"))
      (node (ref "C88") (pin "1") (pinfunction "1_1") (pintype "passive"))
      (node (ref "C89") (pin "1") (pinfunction "1_1") (pintype "passive"))
      (node (ref "C90") (pin "1") (pinfunction "1_1") (pintype "passive"))
      (node (ref "J6") (pin "5") (pinfunction "5_5") (pintype "passive"))
      (node (ref "P37") (pin "3") (pinfunction "3_3") (pintype "passive"))
      (node (ref "P37") (pin "5") (pinfunction "5_5") (pintype "passive"))
      (node (ref "R131") (pin "2") (pinfunction "2_2") (pintype "passive"))
      (node (ref "SD1") (pin "11") (pinfunction "SHLD_11") (pintype "passive"))
      (node (ref "SD1") (pin "12") (pinfunction "SHLD_12") (pintype "passive"))
      (node (ref "SD1") (pin "13") (pinfunction "SHLD_13") (pintype "passive"))
      (node (ref "SD1") (pin "14") (pinfunction "SHLD_14") (pintype "passive"))
      (node (ref "SD1") (pin "6") (pinfunction "VSS_6") (pintype "passive"))
      (node (ref "SW6") (pin "2") (pinfunction "2_2") (pintype "passive"))
      (node (ref "U20") (pin "1") (pinfunction "A0_1") (pintype "input"))
      (node (ref "U20") (pin "2") (pinfunction "A1_2") (pintype "input"))
      (node (ref "U20") (pin "3") (pinfunction "A2_3") (pintype "input"))
      (node (ref "U20") (pin "4") (pinfunction "VSS_4") (pintype "power_in"))
      (node (ref "U20") (pin "7") (pinfunction "WP_7") (pintype "input"))
      (node (ref "U30") (pin "107") (pinfunction "VSS_107") (pintype "power_in"))
      (node (ref "U30") (pin "120") (pinfunction "VSS_120") (pintype "power_in"))
      (node (ref "U30") (pin "130") (pinfunction "VSS_130") (pintype "power_in"))
      (node (ref "U30") (pin "143") (pinfunction "PDR_ON_143") (pintype "input"))
      (node (ref "U30") (pin "16") (pinfunction "VSS_16") (pintype "power_in"))
      (node (ref "U30") (pin "31") (pinfunction "VSSA_31") (pintype "power_in"))
      (node (ref "U30") (pin "38") (pinfunction "VSS_38") (pintype "power_in"))
      (node (ref "U30") (pin "51") (pinfunction "VSS_51") (pintype "power_in"))
      (node (ref "U30") (pin "61") (pinfunction "VSS_61") (pintype "power_in"))
      (node (ref "U30") (pin "83") (pinfunction "VSS_83") (pintype "power_in"))
      (node (ref "U30") (pin "94") (pinfunction "VSS_94") (pintype "power_in"))
      (node (ref "VR3") (pin "1") (pinfunction "GND_1") (pintype "passive"))
      (node (ref "Y1") (pin "2") (pinfunction "GND_1_2") (pintype "passive"))
      (node (ref "Y1") (pin "4") (pinfunction "GND_2_4") (pintype "passive"))
    )
    (net (code "122") (name "Net-(C76-Pad2)") (class "Default")
      (node (ref "C76") (pin "2") (pinfunction "2_2") (pintype "passive"))
      (node (ref "U30") (pin "71") (pinfunction "VCAP_71") (pintype "power_in"))
    )
    (net (code "123") (name "Net-(C77-Pad2)") (class "Default")
      (node (ref "C77") (pin "2") (pinfunction "2_2") (pintype "passive"))
      (node (ref "U30") (pin "106") (pinfunction "VCAP_106") (pintype "power_in"))
    )
    (net (code "124") (name "Net-(U30B-PB2)") (class "Default")
      (node (ref "R170") (pin "2") (pinfunction "2_2") (pintype "passive"))
      (node (ref "U30") (pin "48") (pinfunction "PB2_48") (pintype "bidirectional"))
    )
    (net (code "125") (name "Net-(U30B-PC8)") (class "Default")
      (node (ref "R30") (pin "1") (pinfunction "1_1") (pintype "passive"))
      (node (ref "U30") (pin "98") (pinfunction "PC8_98") (pintype "bidirectional"))
    )
    (net (code "126") (name "Net-(U30B-PC10)") (class "Default")
      (node (ref "R167") (pin "1") (pinfunction "1_1") (pintype "passive"))
      (node (ref "U30") (pin "111") (pinfunction "PC10_111") (pintype "bidirectional"))
    )
    (net (code "127") (name "Net-(U30B-PC11)") (class "Default")
      (node (ref "R168") (pin "1") (pinfunction "1_1") (pintype "passive"))
      (node (ref "U30") (pin "112") (pinfunction "PC11_112") (pintype "bidirectional"))
    )
    (net (code "128") (name "Net-(U30B-PC12)") (class "Default")
      (node (ref "R31") (pin "1") (pinfunction "1_1") (pintype "passive"))
      (node (ref "U30") (pin "113") (pinfunction "PC12_113") (pintype "bidirectional"))
    )
    (net (code "129") (name "Net-(U30C-PE6)") (class "Default")
      (node (ref "R33") (pin "2") (pinfunction "2_2") (pintype "passive"))
      (node (ref "U30") (pin "5") (pinfunction "PE6_5") (pintype "bidirectional"))
    )
    (net (code "130") (name "Net-(U30C-PE12)") (class "Default")
      (node (ref "R34") (pin "2") (pinfunction "2_2") (pintype "passive"))
      (node (ref "U30") (pin "65") (pinfunction "PE12_65") (pintype "bidirectional"))
    )
    (net (code "131") (name "Net-(U30C-PE13)") (class "Default")
      (node (ref "R36") (pin "2") (pinfunction "2_2") (pintype "passive"))
      (node (ref "U30") (pin "66") (pinfunction "PE13_66") (pintype "bidirectional"))
    )
    (net (code "132") (name "unconnected-(J6-Pad3)") (class "Default")
      (node (ref "J6") (pin "3") (pinfunction "3_3") (pintype "passive"))
    )
    (net (code "133") (name "unconnected-(J6-Pad6)") (class "Default")
      (node (ref "J6") (pin "6") (pinfunction "6_6") (pintype "passive"))
    )
    (net (code "134") (name "unconnected-(J6-Pad7)") (class "Default")
      (node (ref "J6") (pin "7") (pinfunction "7_7") (pintype "passive"))
    )
    (net (code "135") (name "unconnected-(J6-Pad8)") (class "Default")
      (node (ref "J6") (pin "8") (pinfunction "8_8") (pintype "passive"))
    )
    (net (code "136") (name "unconnected-(J6-Pad9)") (class "Default")
      (node (ref "J6") (pin "9") (pinfunction "9_9") (pintype "passive"))
    )
    (net (code "137") (name "unconnected-(P37-Pad6)") (class "Default")
      (node (ref "P37") (pin "6") (pinfunction "6_6") (pintype "passive"))
    )
    (net (code "138") (name "unconnected-(P37-Pad7)") (class "Default")
      (node (ref "P37") (pin "7") (pinfunction "7_7") (pintype "passive"))
    )
    (net (code "139") (name "unconnected-(P37-Pad8)") (class "Default")
      (node (ref "P37") (pin "8") (pinfunction "8_8") (pintype "passive"))
    )
    (net (code "140") (name "unconnected-(P37-Pad9)") (class "Default")
      (node (ref "P37") (pin "9") (pinfunction "9_9") (pintype "passive"))
    )
    (net (code "141") (name "unconnected-(SD1-CD_A-Pad9)") (class "Default")
      (node (ref "SD1") (pin "9") (pinfunction "CD_A_9") (pintype "passive"))
    )
    (net (code "142") (name "unconnected-(SD1-CD_B-Pad10)") (class "Default")
      (node (ref "SD1") (pin "10") (pinfunction "CD_B_10") (pintype "passive"))
    )
    (net (code "143") (name "unconnected-(SD1-CD{slash}DAT3-Pad2)") (class "Default")
      (node (ref "SD1") (pin "2") (pinfunction "CD/DAT3_2") (pintype "passive"))
    )
    (net (code "144") (name "unconnected-(SD1-DAT1-Pad8)") (class "Default")
      (node (ref "SD1") (pin "8") (pinfunction "DAT1_8") (pintype "passive"))
    )
    (net (code "145") (name "unconnected-(SD1-DAT2-Pad1)") (class "Default")
      (node (ref "SD1") (pin "1") (pinfunction "DAT2_1") (pintype "passive"))
    )
    (net (code "146") (name "unconnected-(SW5-Pad3)") (class "Default")
      (node (ref "SW5") (pin "3") (pinfunction "3_3") (pintype "passive"))
    )
    (net (code "147") (name "unconnected-(SW5-PadMP1)") (class "Default")
      (node (ref "SW5") (pin "MP1") (pinfunction "MP1_MP1") (pintype "passive"))
    )
    (net (code "148") (name "unconnected-(SW5-PadMP2)") (class "Default")
      (node (ref "SW5") (pin "MP2") (pinfunction "MP2_MP2") (pintype "passive"))
    )
    (net (code "149") (name "unconnected-(SW6-PadMP1)") (class "Default")
      (node (ref "SW6") (pin "MP1") (pinfunction "MP1_MP1") (pintype "passive"))
    )
    (net (code "150") (name "unconnected-(SW6-PadMP2)") (class "Default")
      (node (ref "SW6") (pin "MP2") (pinfunction "MP2_MP2") (pintype "passive"))
    )
  )
)
